# orienteringsklokke_v2.net
KiCad netlist of a schematic drawn in EAGLE
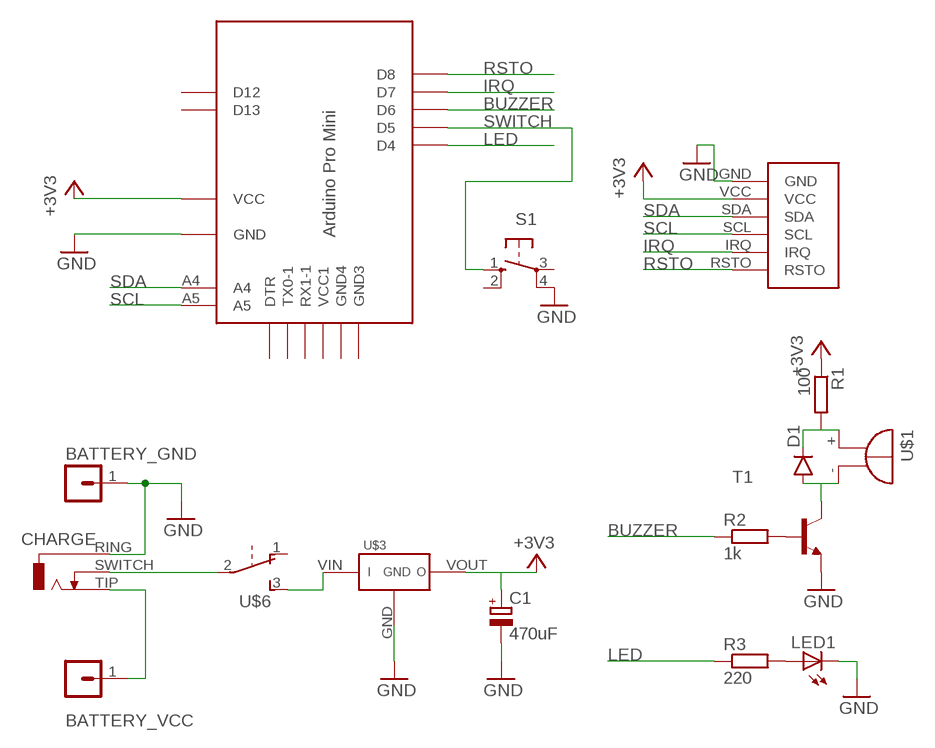
[diagram p0: schematic, sheet 1]

(export (version "E")
  (design (tool "Eeschema 10.0.6"))
  (components
    (comp (ref "BATTERY_GND")
      (value "MA01-1JC")
      (footprint "eagle-import:MA01-1J")
      (libsource (lib "eagle-import") (part "MA01-1JC"))
    )
    (comp (ref "BATTERY_VCC")
      (value "MA01-1JC")
      (footprint "eagle-import:MA01-1J")
      (libsource (lib "eagle-import") (part "MA01-1JC"))
    )
    (comp (ref "C1")
      (value "470uF")
      (footprint "eagle-import:E2,5-6")
      (libsource (lib "eagle-import") (part "CPOL-EUE2.5-6"))
    )
    (comp (ref "CHARGE")
      (value "ST613-JACK")
      (footprint "eagle-import:ST613-JACK")
      (libsource (lib "eagle-import") (part "ST613-JACK"))
    )
    (comp (ref "D1")
      (value "1N4148DOJ35-5")
      (footprint "eagle-import:DO35-5J")
      (libsource (lib "eagle-import") (part "1N4148DOJ35-5"))
    )
    (comp (ref "LED1")
      (value "LED3MM")
      (footprint "eagle-import:LED3MM")
      (libsource (lib "eagle-import") (part "LED3MM"))
    )
    (comp (ref "R1")
      (value "100")
      (footprint "eagle-import:0207_7")
      (libsource (lib "eagle-import") (part "R-EU_0207/7"))
    )
    (comp (ref "R2")
      (value "1k")
      (footprint "eagle-import:0207_7")
      (libsource (lib "eagle-import") (part "R-EU_0207/7"))
    )
    (comp (ref "R3")
      (value "220")
      (footprint "eagle-import:0207_7")
      (libsource (lib "eagle-import") (part "R-EU_0207/7"))
    )
    (comp (ref "S1")
      (value "10-XX")
      (footprint "eagle-import:B3F-10XX")
      (fields (field (name "MPN") "B3F-1000"))
      (libsource (lib "eagle-import") (part "10-XX"))
    )
    (comp (ref "T1")
      (value "2N3904-NPN-TO92-EBC")
      (footprint "eagle-import:TO92-EBC")
      (libsource (lib "eagle-import") (part "-NPN-TO92-EBC2N3904"))
    )
    (comp (ref "U$1")
      (value "BUZZER_J")
      (footprint "eagle-import:BUZZER_J")
      (libsource (lib "eagle-import") (part "BUZZER_J"))
    )
    (comp (ref "U$2")
      (value "NFC_MODULE_V3_I2C")
      (footprint "eagle-import:NFC_MODULE_V3_I2C")
      (libsource (lib "eagle-import") (part "NFC_MODULE_V3_I2C"))
    )
    (comp (ref "U$3")
      (value "VOLT_BOOST")
      (footprint "eagle-import:VOLT-BOOST")
      (libsource (lib "eagle-import") (part "VOLT_BOOST"))
    )
    (comp (ref "U$4")
      (value "ARD-PRO-MINI-ORIENTERING")
      (footprint "eagle-import:ARD_PRO_MINI_ORIENTERING")
      (libsource (lib "eagle-import") (part "ARD-PRO-MINI-ORIENTERING"))
    )
    (comp (ref "U$6")
      (value "SK12D07-SLIDE-SWITCH")
      (footprint "eagle-import:SK12D07")
      (libsource (lib "eagle-import") (part "SK12D07-SLIDE-SWITCH"))
    )
  )
  (nets
    (net (code "1") (name "+3V3") (class "Default")
      (node (ref "C1") (pin "+") (pinfunction "+_+") (pintype "passive"))
      (node (ref "R1") (pin "1") (pinfunction "1_1") (pintype "passive"))
      (node (ref "U$2") (pin "VCC") (pinfunction "VCC_VCC") (pintype "bidirectional"))
      (node (ref "U$3") (pin "VOUT") (pinfunction "VOUT_VOUT") (pintype "bidirectional"))
      (node (ref "U$4") (pin "VCC") (pinfunction "VCC_VCC") (pintype "bidirectional"))
    )
    (net (code "2") (name "BUZZER") (class "Default")
      (node (ref "R2") (pin "1") (pinfunction "1_1") (pintype "passive"))
      (node (ref "U$4") (pin "D6") (pinfunction "D6_D6") (pintype "bidirectional"))
    )
    (net (code "3") (name "GND") (class "Default")
      (node (ref "BATTERY_GND") (pin "1") (pinfunction "1_1") (pintype "passive"))
      (node (ref "C1") (pin "-") (pinfunction "-_-") (pintype "passive"))
      (node (ref "CHARGE") (pin "RING") (pinfunction "1_RING") (pintype "passive"))
      (node (ref "LED1") (pin "K") (pinfunction "C_K") (pintype "passive"))
      (node (ref "S1") (pin "4") (pinfunction "P1_4") (pintype "passive"))
      (node (ref "T1") (pin "E") (pinfunction "E_E") (pintype "passive"))
      (node (ref "U$2") (pin "GND") (pinfunction "GND_GND") (pintype "bidirectional"))
      (node (ref "U$3") (pin "GND") (pinfunction "GND_GND") (pintype "bidirectional"))
      (node (ref "U$4") (pin "GND") (pinfunction "GND_GND") (pintype "bidirectional"))
    )
    (net (code "4") (name "IRQ") (class "Default")
      (node (ref "U$2") (pin "IRQ") (pinfunction "IRQ_IRQ") (pintype "bidirectional"))
      (node (ref "U$4") (pin "D7") (pinfunction "D7_D7") (pintype "bidirectional"))
    )
    (net (code "5") (name "LED") (class "Default")
      (node (ref "R3") (pin "1") (pinfunction "1_1") (pintype "passive"))
      (node (ref "U$4") (pin "D4") (pinfunction "D4_D4") (pintype "bidirectional"))
    )
    (net (code "6") (name "Net-(CHARGE-2)") (class "Default")
      (node (ref "CHARGE") (pin "SWITCH") (pinfunction "2_SWITCH") (pintype "passive"))
      (node (ref "U$6") (pin "2") (pinfunction "2_2") (pintype "passive"))
    )
    (net (code "7") (name "Net-(CHARGE-3)") (class "Default")
      (node (ref "BATTERY_VCC") (pin "1") (pinfunction "1_1") (pintype "passive"))
      (node (ref "CHARGE") (pin "TIP") (pinfunction "3_TIP") (pintype "passive"))
    )
    (net (code "8") (name "Net-(D1-PadA)") (class "Default")
      (node (ref "D1") (pin "A") (pinfunction "A_A") (pintype "passive"))
      (node (ref "T1") (pin "C") (pinfunction "C_C") (pintype "passive"))
      (node (ref "U$1") (pin "-") (pinfunction "-_-") (pintype "passive"))
    )
    (net (code "9") (name "Net-(D1-PadC)") (class "Default")
      (node (ref "D1") (pin "C") (pinfunction "C_C") (pintype "passive"))
      (node (ref "R1") (pin "2") (pinfunction "2_2") (pintype "passive"))
      (node (ref "U$1") (pin "+") (pinfunction "+_+") (pintype "passive"))
    )
    (net (code "10") (name "Net-(LED1-PadA)") (class "Default")
      (node (ref "LED1") (pin "A") (pinfunction "A_A") (pintype "passive"))
      (node (ref "R3") (pin "2") (pinfunction "2_2") (pintype "passive"))
    )
    (net (code "11") (name "Net-(R2-Pad2)") (class "Default")
      (node (ref "R2") (pin "2") (pinfunction "2_2") (pintype "passive"))
      (node (ref "T1") (pin "B") (pinfunction "B_B") (pintype "passive"))
    )
    (net (code "12") (name "Net-(U$3-PadVIN)") (class "Default")
      (node (ref "U$3") (pin "VIN") (pinfunction "VIN_VIN") (pintype "bidirectional"))
      (node (ref "U$6") (pin "3") (pinfunction "3_3") (pintype "passive"))
    )
    (net (code "13") (name "RSTO") (class "Default")
      (node (ref "U$2") (pin "RSTO") (pinfunction "RSTO_RSTO") (pintype "bidirectional"))
      (node (ref "U$4") (pin "D8") (pinfunction "D8_D8") (pintype "bidirectional"))
    )
    (net (code "14") (name "SCL") (class "Default")
      (node (ref "U$2") (pin "SCL") (pinfunction "SCL_SCL") (pintype "bidirectional"))
      (node (ref "U$4") (pin "A5") (pinfunction "A5_A5") (pintype "bidirectional"))
    )
    (net (code "15") (name "SDA") (class "Default")
      (node (ref "U$2") (pin "SDA") (pinfunction "SDA_SDA") (pintype "bidirectional"))
      (node (ref "U$4") (pin "A4") (pinfunction "A4_A4") (pintype "bidirectional"))
    )
    (net (code "16") (name "SWITCH") (class "Default")
      (node (ref "S1") (pin "1") (pinfunction "S_1") (pintype "passive"))
      (node (ref "U$4") (pin "D5") (pinfunction "D5_D5") (pintype "bidirectional"))
    )
    (net (code "17") (name "unconnected-(S1-P-Pad3)") (class "Default")
      (node (ref "S1") (pin "3") (pinfunction "P_3") (pintype "passive"))
    )
    (net (code "18") (name "unconnected-(S1-S1-Pad2)") (class "Default")
      (node (ref "S1") (pin "2") (pinfunction "S1_2") (pintype "passive"))
    )
    (net (code "19") (name "unconnected-(U$4-GND3-PadGND2)") (class "Default")
      (node (ref "U$4") (pin "GND2") (pinfunction "GND3_GND2") (pintype "bidirectional"))
    )
    (net (code "20") (name "unconnected-(U$4-GND4-PadGND3)") (class "Default")
      (node (ref "U$4") (pin "GND3") (pinfunction "GND4_GND3") (pintype "bidirectional"))
    )
    (net (code "21") (name "unconnected-(U$4-PadD12)") (class "Default")
      (node (ref "U$4") (pin "D12") (pinfunction "D12_D12") (pintype "bidirectional"))
    )
    (net (code "22") (name "unconnected-(U$4-PadD13)") (class "Default")
      (node (ref "U$4") (pin "D13") (pinfunction "D13_D13") (pintype "bidirectional"))
    )
    (net (code "23") (name "unconnected-(U$4-PadDTR)") (class "Default")
      (node (ref "U$4") (pin "DTR") (pinfunction "DTR_DTR") (pintype "bidirectional"))
    )
    (net (code "24") (name "unconnected-(U$4-PadRX1-1)") (class "Default")
      (node (ref "U$4") (pin "RX1-1") (pinfunction "RX1-1_RX1-1") (pintype "bidirectional"))
    )
    (net (code "25") (name "unconnected-(U$4-PadTX0-1)") (class "Default")
      (node (ref "U$4") (pin "TX0-1") (pinfunction "TX0-1_TX0-1") (pintype "bidirectional"))
    )
    (net (code "26") (name "unconnected-(U$4-PadVCC1)") (class "Default")
      (node (ref "U$4") (pin "VCC1") (pinfunction "VCC1_VCC1") (pintype "bidirectional"))
    )
    (net (code "27") (name "unconnected-(U$6-Pad1)") (class "Default")
      (node (ref "U$6") (pin "1") (pinfunction "1_1") (pintype "passive"))
    )
  )
)
